# Teensy32.net
KiCad netlist of a schematic drawn in Altium Designer
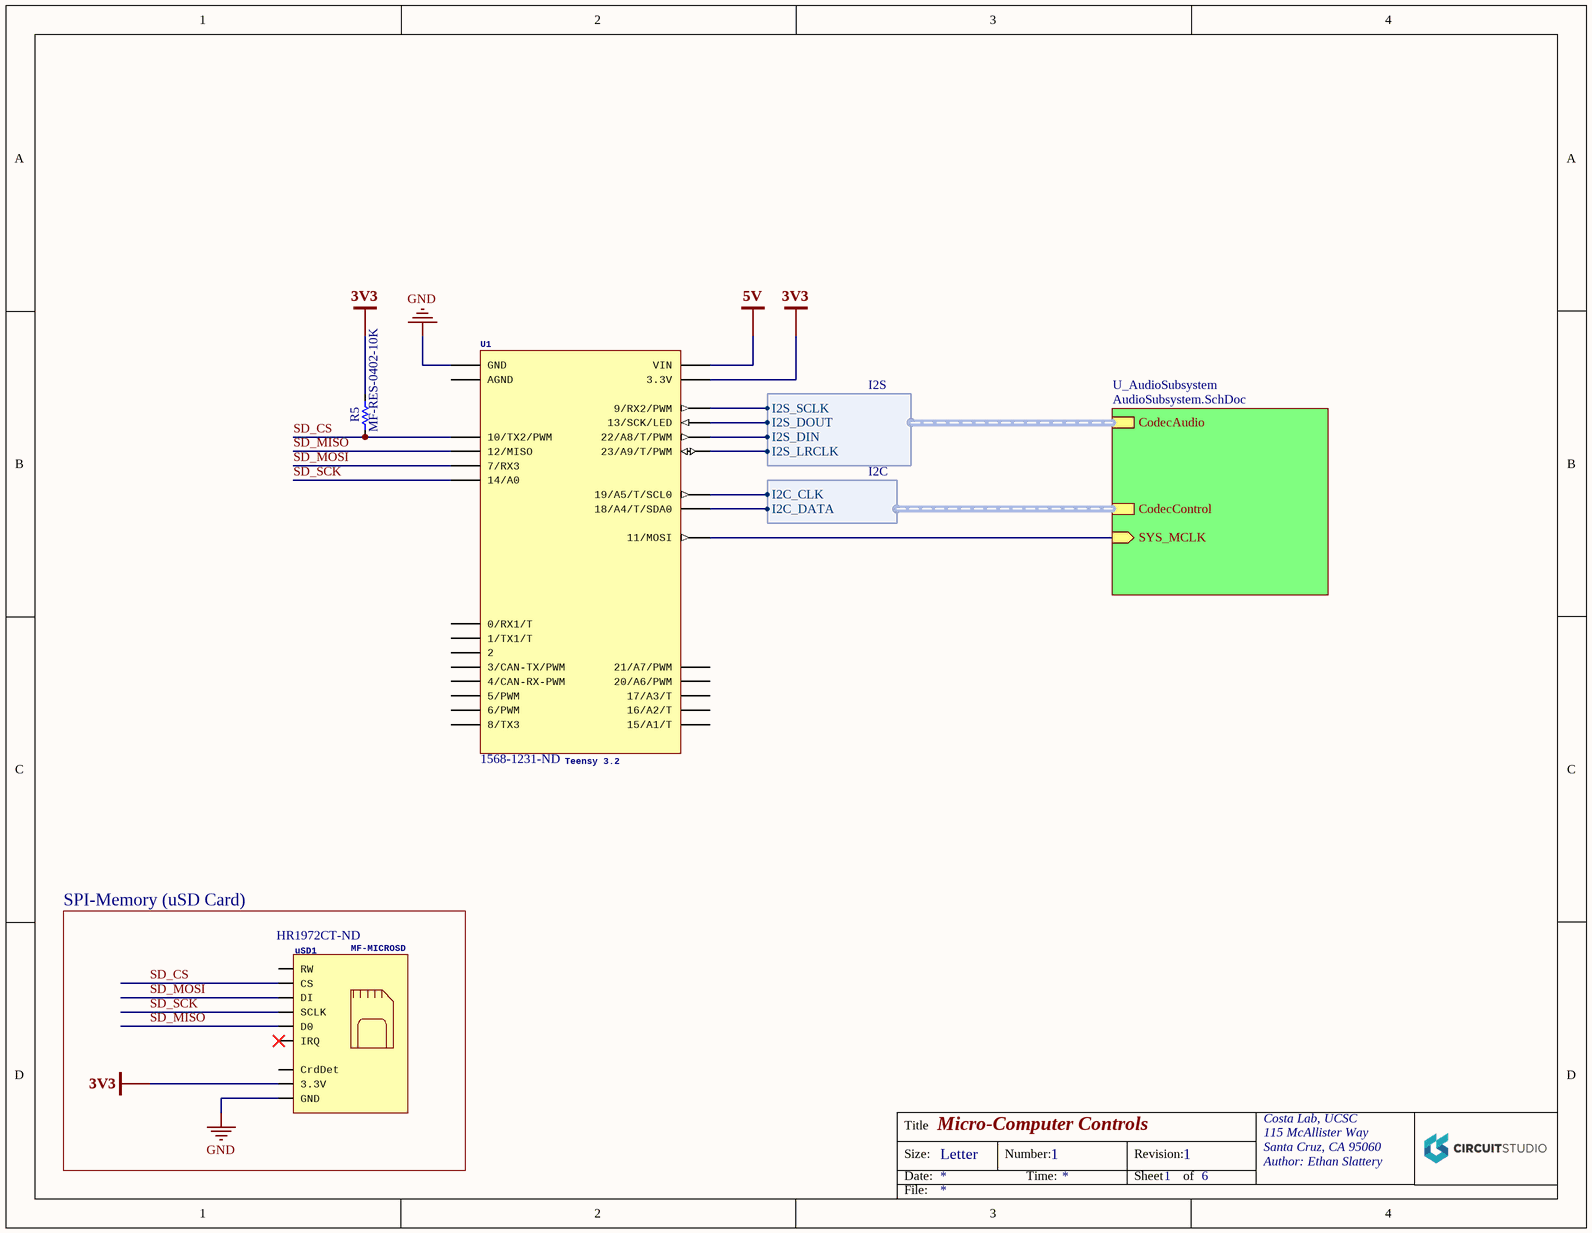
[diagram p0: Teensy32.SchDoc]

(export (version "E")
  (design (tool "Eeschema 10.0.6"))
  (components
    (comp (ref "R5")
      (value "MF-RES-0402-10K")
      (footprint "R0402L")
      (fields (field (name "HOUSEPART") "YES") (field (name "VOLTAGE") "50 V"))
      (libsource (lib "MF_Passives") (part "RESISTOR"))
    )
    (comp (ref "U1")
      (value "Teensy 3.2")
      (footprint "TEENSY_3.0-3.2&LC_DIL")
      (fields (field (name "SUPPLIER PART NUMBER 1") "1568-1231-ND") (field (name "HOUSEPART") "NO"))
      (libsource (lib "BreakoutBoards") (part "TEENSY 3.2"))
    )
    (comp (ref "uSD1")
      (value "MF-MICROSD")
      (footprint "MF-MICROSD")
      (description "Actual Device is 4UCONN microSD")
      (fields (field (name "HOUSEPART") "YES") (field (name "SUPPLIER PART NUMBER 1") "HR1972CT-ND"))
      (libsource (lib "Connectors") (part "MacroFab uSD card slot"))
    )
  )
  (nets
    (net (code "3") (name "/I2C_CLK") (class "Default")
      (node (ref "U1") (pin "19/A5") (pinfunction "19/A5/T/SCL0_19/A5") (pintype "output"))
    )
    (net (code "4") (name "/I2C_DATA") (class "Default")
      (node (ref "U1") (pin "18/A4") (pinfunction "18/A4/T/SDA0_18/A4") (pintype "passive"))
    )
    (net (code "5") (name "/I2S_DIN") (class "Default")
      (node (ref "U1") (pin "22/A8") (pinfunction "22/A8/T/PWM_22/A8") (pintype "output"))
    )
    (net (code "6") (name "/I2S_DOUT") (class "Default")
      (node (ref "U1") (pin "13") (pinfunction "13/SCK/LED_13") (pintype "input"))
    )
    (net (code "7") (name "/I2S_LRCLK") (class "Default")
      (node (ref "U1") (pin "23/A9") (pinfunction "23/A9/T/PWM_23/A9") (pintype "bidirectional"))
    )
    (net (code "8") (name "/I2S_SCLK") (class "Default")
      (node (ref "U1") (pin "9") (pinfunction "9/RX2/PWM_9") (pintype "output"))
    )
    (net (code "9") (name "/SD_CS") (class "Default")
      (node (ref "R5") (pin "1") (pinfunction "1_1") (pintype "passive"))
      (node (ref "U1") (pin "10") (pinfunction "10/TX2/PWM_10") (pintype "passive"))
      (node (ref "uSD1") (pin "2") (pinfunction "CS_2") (pintype "passive"))
    )
    (net (code "10") (name "/SD_MISO") (class "Default")
      (node (ref "U1") (pin "12") (pinfunction "12/MISO_12") (pintype "passive"))
      (node (ref "uSD1") (pin "7") (pinfunction "D0_7") (pintype "passive"))
    )
    (net (code "11") (name "/SD_MOSI") (class "Default")
      (node (ref "U1") (pin "7") (pinfunction "7/RX3_7") (pintype "passive"))
      (node (ref "uSD1") (pin "3") (pinfunction "DI_3") (pintype "passive"))
    )
    (net (code "12") (name "/SD_SCK") (class "Default")
      (node (ref "U1") (pin "14/A0") (pinfunction "14/A0_14/A0") (pintype "passive"))
      (node (ref "uSD1") (pin "5") (pinfunction "SCLK_5") (pintype "passive"))
    )
    (net (code "13") (name "/SYS_MCLK") (class "Default")
      (node (ref "U1") (pin "11") (pinfunction "11/MOSI_11") (pintype "output"))
    )
    (net (code "16") (name "3V3") (class "Default")
      (node (ref "R5") (pin "2") (pinfunction "2_2") (pintype "passive"))
      (node (ref "U1") (pin "3.3V") (pinfunction "3.3V_3.3V") (pintype "power_in"))
      (node (ref "uSD1") (pin "3.3V") (pinfunction "3.3V_3.3V") (pintype "power_in"))
    )
    (net (code "17") (name "5V") (class "Default")
      (node (ref "U1") (pin "VIN") (pinfunction "VIN_VIN") (pintype "power_in"))
    )
    (net (code "18") (name "GND") (class "Default")
      (node (ref "U1") (pin "GND") (pinfunction "GND_GND") (pintype "power_in"))
      (node (ref "uSD1") (pin "GND") (pinfunction "GND_GND") (pintype "power_in"))
    )
    (net (code "19") (name "unconnected-(U1-0{slash}RX1{slash}T-Pad0)") (class "Default")
      (node (ref "U1") (pin "0") (pinfunction "0/RX1/T_0") (pintype "passive"))
    )
    (net (code "20") (name "unconnected-(U1-1{slash}TX1{slash}T-Pad1)") (class "Default")
      (node (ref "U1") (pin "1") (pinfunction "1/TX1/T_1") (pintype "passive"))
    )
    (net (code "21") (name "unconnected-(U1-3{slash}CAN-TX{slash}PWM-Pad3)") (class "Default")
      (node (ref "U1") (pin "3") (pinfunction "3/CAN-TX/PWM_3") (pintype "passive"))
    )
    (net (code "22") (name "unconnected-(U1-4{slash}CAN-RX-PWM-Pad4)") (class "Default")
      (node (ref "U1") (pin "4") (pinfunction "4/CAN-RX-PWM_4") (pintype "passive"))
    )
    (net (code "23") (name "unconnected-(U1-5{slash}PWM-Pad5)") (class "Default")
      (node (ref "U1") (pin "5") (pinfunction "5/PWM_5") (pintype "passive"))
    )
    (net (code "24") (name "unconnected-(U1-6{slash}PWM-Pad6)") (class "Default")
      (node (ref "U1") (pin "6") (pinfunction "6/PWM_6") (pintype "passive"))
    )
    (net (code "25") (name "unconnected-(U1-8{slash}TX3-Pad8)") (class "Default")
      (node (ref "U1") (pin "8") (pinfunction "8/TX3_8") (pintype "passive"))
    )
    (net (code "26") (name "unconnected-(U1-15{slash}A1{slash}T-Pad15{slash}A1)") (class "Default")
      (node (ref "U1") (pin "15/A1") (pinfunction "15/A1/T_15/A1") (pintype "passive"))
    )
    (net (code "27") (name "unconnected-(U1-16{slash}A2{slash}T-Pad16{slash}A2)") (class "Default")
      (node (ref "U1") (pin "16/A2") (pinfunction "16/A2/T_16/A2") (pintype "passive"))
    )
    (net (code "28") (name "unconnected-(U1-17{slash}A3{slash}T-Pad17{slash}A3)") (class "Default")
      (node (ref "U1") (pin "17/A3") (pinfunction "17/A3/T_17/A3") (pintype "passive"))
    )
    (net (code "29") (name "unconnected-(U1-20{slash}A6{slash}PWM-Pad20{slash}A6)") (class "Default")
      (node (ref "U1") (pin "20/A6") (pinfunction "20/A6/PWM_20/A6") (pintype "passive"))
    )
    (net (code "30") (name "unconnected-(U1-21{slash}A7{slash}PWM-Pad21{slash}A7)") (class "Default")
      (node (ref "U1") (pin "21/A7") (pinfunction "21/A7/PWM_21/A7") (pintype "passive"))
    )
    (net (code "31") (name "unconnected-(U1-Pad2)") (class "Default")
      (node (ref "U1") (pin "2") (pinfunction "2_2") (pintype "passive"))
    )
    (net (code "32") (name "unconnected-(U1-PadAGND)") (class "Default")
      (node (ref "U1") (pin "AGND") (pinfunction "AGND_AGND") (pintype "power_in"))
    )
    (net (code "33") (name "unconnected-(uSD1-IRQ-Pad8)") (class "Default")
      (node (ref "uSD1") (pin "8") (pinfunction "IRQ_8") (pintype "passive+no_connect"))
    )
    (net (code "34") (name "unconnected-(uSD1-PadCrdDet)") (class "Default")
      (node (ref "uSD1") (pin "CrdDet") (pinfunction "CrdDet_CrdDet") (pintype "passive"))
    )
    (net (code "35") (name "unconnected-(uSD1-RW-Pad1)") (class "Default")
      (node (ref "uSD1") (pin "1") (pinfunction "RW_1") (pintype "passive"))
    )
  )
)
